# C_PITCHROLLER.net
KiCad netlist of a schematic drawn in Altium Designer
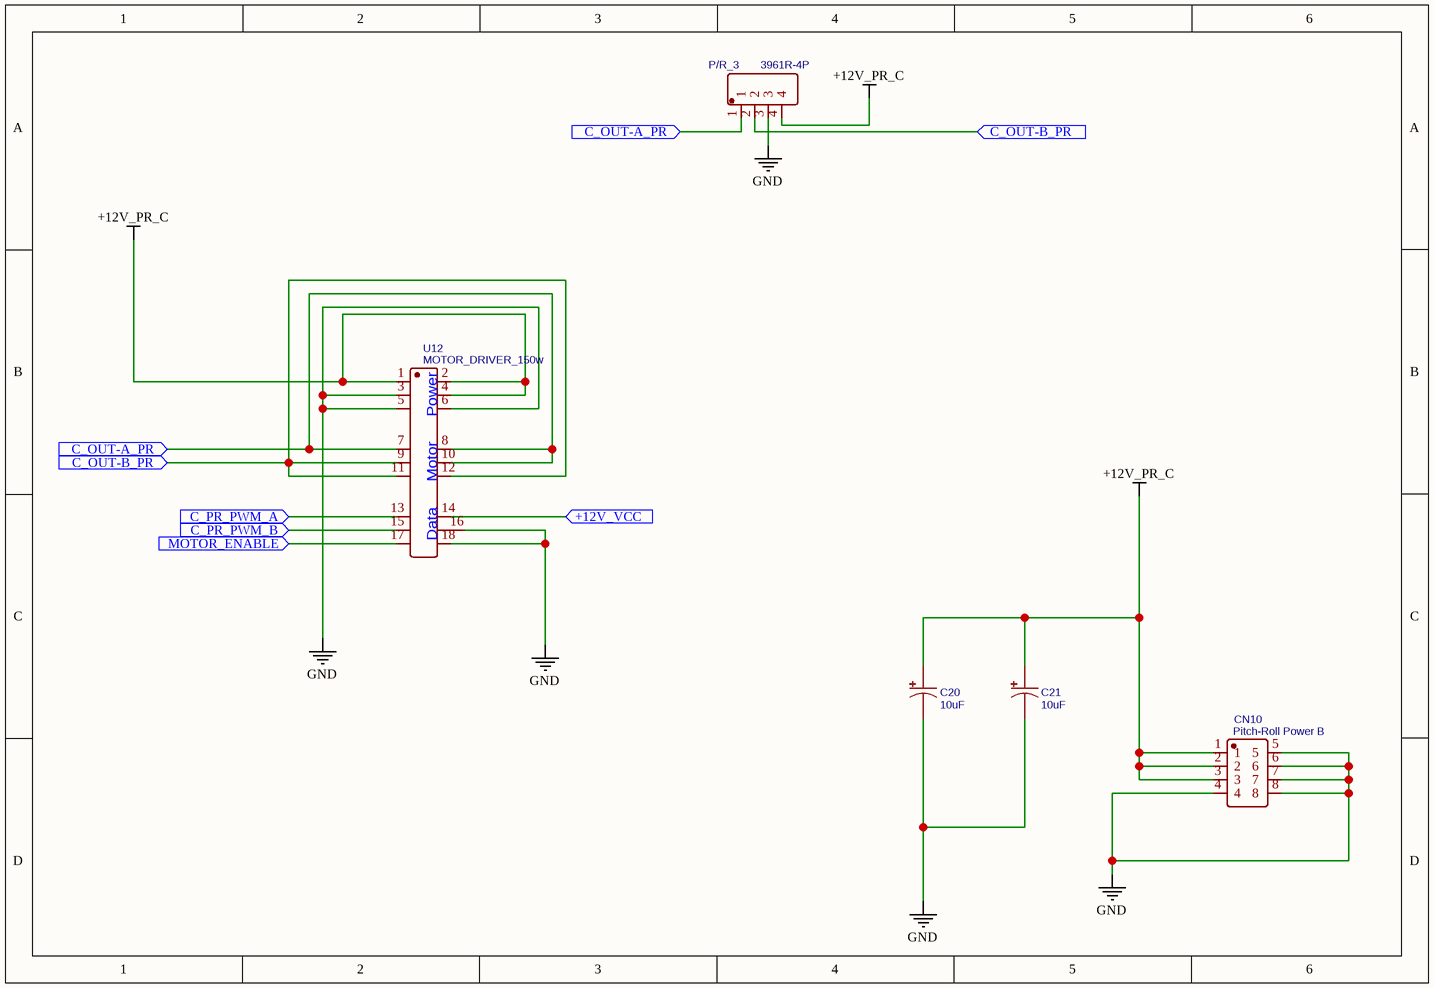
[diagram p0: C_PITCHROLLER.schdoc]

(export (version "E")
  (design (tool "Eeschema 10.0.6"))
  (components
    (comp (ref "C20")
      (value "10uF")
      (fields
        (field (name "BOM_SUPPLIER PART") "C213486")
        (field (name "BOM_MANUFACTURER PART") "VT1E100M0405")
        (field (name "CONTRIBUTOR") "LCSC")
      )
      (libsource (lib "altium-import") (part "root_1_10uF_"))
    )
    (comp (ref "C21")
      (value "10uF")
      (fields
        (field (name "BOM_SUPPLIER PART") "C213486")
        (field (name "BOM_MANUFACTURER PART") "VT1E100M0405")
        (field (name "CONTRIBUTOR") "LCSC")
      )
      (libsource (lib "altium-import") (part "root_1_10uF_"))
    )
    (comp (ref "CN10")
      (value "Pitch-Roll Power B")
      (fields
        (field (name "BOM_SUPPLIER PART") "C519240")
        (field (name "BOM_MANUFACTURER PART") "X9357WV-2*04-N2SN")
        (field (name "CONTRIBUTOR") "LCSC")
      )
      (libsource (lib "altium-import") (part "root_0_Pitch-Roll Power B_"))
    )
    (comp (ref "P/R_3")
      (value "3961R-4P")
      (fields (field (name "BOM_SUPPLIER PART") "C138427") (field (name "CONTRIBUTOR") "LCSC"))
      (libsource (lib "altium-import") (part "root_1_3961R-4P_"))
    )
    (comp (ref "U12")
      (value "MOTOR_DRIVER_150w")
      (fields (field (name "CONTRIBUTOR") "digitalman"))
      (libsource (lib "altium-import") (part "root_3_MOTOR_DRIVER_150w_"))
    )
  )
  (nets
    (net (code "1") (name "+12V_PR_C") (class "Default")
      (node (ref "C20") (pin "1") (pinfunction "1_1") (pintype "passive"))
      (node (ref "C21") (pin "1") (pinfunction "1_1") (pintype "passive"))
      (node (ref "CN10") (pin "1") (pinfunction "1_1") (pintype "passive"))
      (node (ref "CN10") (pin "2") (pinfunction "2_2") (pintype "passive"))
      (node (ref "CN10") (pin "3") (pinfunction "3_3") (pintype "passive"))
      (node (ref "P/R_3") (pin "4") (pinfunction "4_4") (pintype "passive"))
      (node (ref "U12") (pin "1") (pinfunction "+12V_YAW_1") (pintype "passive"))
      (node (ref "U12") (pin "2") (pinfunction "+12V_YAW_2") (pintype "passive"))
      (node (ref "U12") (pin "4") (pinfunction "+12V_YAW_4") (pintype "passive"))
    )
    (net (code "2") (name "/+12V_VCC") (class "Default")
      (node (ref "U12") (pin "14") (pinfunction "+12V_VCC_14") (pintype "passive"))
    )
    (net (code "3") (name "/C_OUT-A_PR") (class "Default")
      (node (ref "P/R_3") (pin "1") (pinfunction "1_1") (pintype "passive"))
      (node (ref "U12") (pin "10") (pinfunction "OUT-A_YAW_10") (pintype "passive"))
      (node (ref "U12") (pin "7") (pinfunction "OUT-A_YAW_7") (pintype "passive"))
      (node (ref "U12") (pin "8") (pinfunction "OUT-A_YAW_8") (pintype "passive"))
    )
    (net (code "4") (name "/C_OUT-B_PR") (class "Default")
      (node (ref "P/R_3") (pin "2") (pinfunction "2_2") (pintype "passive"))
      (node (ref "U12") (pin "11") (pinfunction "OUT-B_YAW_11") (pintype "passive"))
      (node (ref "U12") (pin "12") (pinfunction "OUT-B_YAW_12") (pintype "passive"))
      (node (ref "U12") (pin "9") (pinfunction "OUT-B_YAW_9") (pintype "passive"))
    )
    (net (code "5") (name "/C_PR_PWM_A") (class "Default")
      (node (ref "U12") (pin "13") (pinfunction "PWM-A_YAW_13") (pintype "passive"))
    )
    (net (code "6") (name "/C_PR_PWM_B") (class "Default")
      (node (ref "U12") (pin "15") (pinfunction "PWM-B_YAW_15") (pintype "passive"))
    )
    (net (code "7") (name "/MOTOR_ENABLE") (class "Default")
      (node (ref "U12") (pin "17") (pinfunction "MOTOR_ENABLE_17") (pintype "passive"))
    )
    (net (code "8") (name "GND") (class "Default")
      (node (ref "C20") (pin "2") (pinfunction "2_2") (pintype "passive"))
      (node (ref "C21") (pin "2") (pinfunction "2_2") (pintype "passive"))
      (node (ref "CN10") (pin "4") (pinfunction "4_4") (pintype "passive"))
      (node (ref "CN10") (pin "5") (pinfunction "5_5") (pintype "passive"))
      (node (ref "CN10") (pin "6") (pinfunction "6_6") (pintype "passive"))
      (node (ref "CN10") (pin "7") (pinfunction "7_7") (pintype "passive"))
      (node (ref "CN10") (pin "8") (pinfunction "8_8") (pintype "passive"))
      (node (ref "P/R_3") (pin "3") (pinfunction "3_3") (pintype "passive"))
      (node (ref "U12") (pin "16") (pinfunction "GND_16") (pintype "passive"))
      (node (ref "U12") (pin "18") (pinfunction "GND_18") (pintype "passive"))
      (node (ref "U12") (pin "3") (pinfunction "GND_3") (pintype "passive"))
      (node (ref "U12") (pin "5") (pinfunction "GND_5") (pintype "passive"))
      (node (ref "U12") (pin "6") (pinfunction "GND_6") (pintype "passive"))
    )
  )
)
